# BandpassedGainAmpSMTMounthole.net
KiCad netlist of a schematic drawn in EAGLE
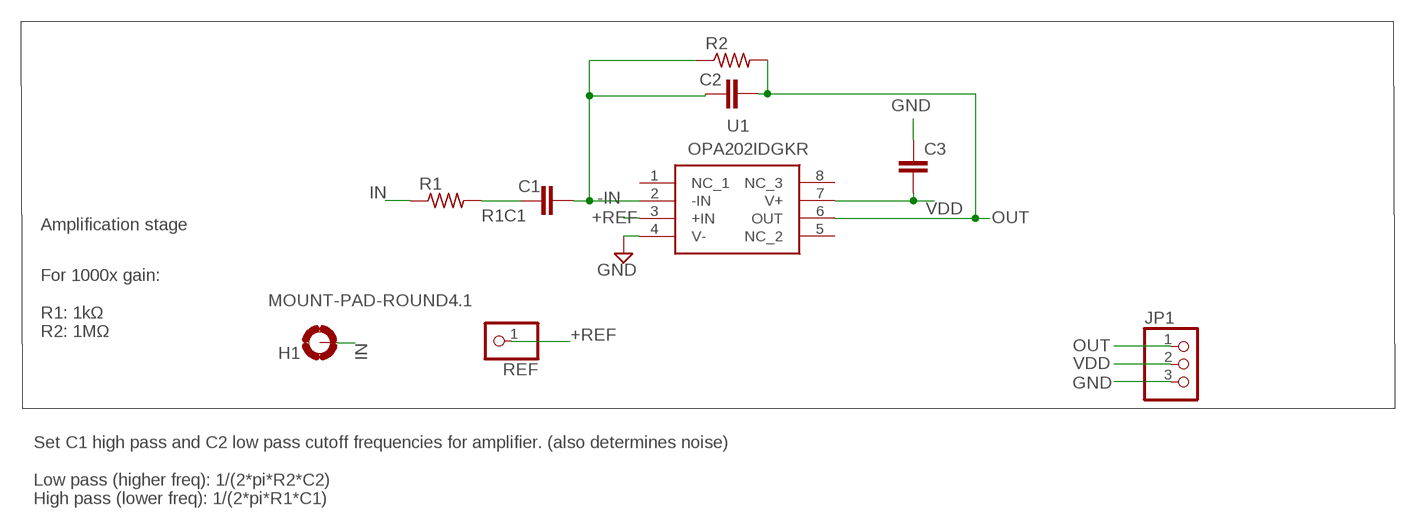
[diagram p0: schematic, sheet 1]

(export (version "E")
  (design (tool "Eeschema 10.0.6"))
  (components
    (comp (ref "C1")
      (value "C-EUC0402")
      (footprint "eagle-import:C0402")
      (libsource (lib "eagle-import") (part "C-EUC0402"))
    )
    (comp (ref "C2")
      (value "C-EUC0402")
      (footprint "eagle-import:C0402")
      (libsource (lib "eagle-import") (part "C-EUC0402"))
    )
    (comp (ref "C3")
      (value "C-EUC0402")
      (footprint "eagle-import:C0402")
      (libsource (lib "eagle-import") (part "C-EUC0402"))
    )
    (comp (ref "H1")
      (value "MOUNT-PAD-ROUND4.1")
      (footprint "eagle-import:4,1-PAD")
      (libsource (lib "eagle-import") (part "MOUNT-PAD-ROUND4.1"))
    )
    (comp (ref "JP1")
      (value "PINHD-1X3")
      (footprint "eagle-import:1X03")
      (libsource (lib "eagle-import") (part "PINHD-1X3"))
    )
    (comp (ref "R1")
      (value "R-US_R0402")
      (footprint "eagle-import:R0402")
      (libsource (lib "eagle-import") (part "R-US_R0402"))
    )
    (comp (ref "R2")
      (value "R-US_R0402")
      (footprint "eagle-import:R0402")
      (libsource (lib "eagle-import") (part "R-US_R0402"))
    )
    (comp (ref "REF")
      (value "PINHD-1X1")
      (footprint "eagle-import:1X01")
      (libsource (lib "eagle-import") (part "PINHD-1X1"))
    )
    (comp (ref "U1")
      (value "OPA202IDGKR")
      (footprint "eagle-import:SOP65P490X110-8N")
      (fields (field (name "MOUSER_PART_NUMBER") "595-OPA202IDGKR"))
      (libsource (lib "eagle-import") (part "OPA202IDGKR"))
    )
  )
  (nets
    (net (code "1") (name "/+REF") (class "Default")
      (node (ref "REF") (pin "1") (pinfunction "1_1") (pintype "passive"))
      (node (ref "U1") (pin "3") (pinfunction "+IN_3") (pintype "bidirectional"))
    )
    (net (code "2") (name "/-IN") (class "Default")
      (node (ref "C1") (pin "2") (pinfunction "2_2") (pintype "passive"))
      (node (ref "C2") (pin "1") (pinfunction "1_1") (pintype "passive"))
      (node (ref "R2") (pin "1") (pinfunction "1_1") (pintype "passive"))
      (node (ref "U1") (pin "2") (pinfunction "-IN_2") (pintype "bidirectional"))
    )
    (net (code "3") (name "/IN") (class "Default")
      (node (ref "H1") (pin "B4,1") (pinfunction "MOUNT_B4,1") (pintype "passive"))
      (node (ref "R1") (pin "1") (pinfunction "1_1") (pintype "passive"))
    )
    (net (code "4") (name "/OUT") (class "Default")
      (node (ref "C2") (pin "2") (pinfunction "2_2") (pintype "passive"))
      (node (ref "JP1") (pin "1") (pinfunction "1_1") (pintype "passive"))
      (node (ref "R2") (pin "2") (pinfunction "2_2") (pintype "passive"))
      (node (ref "U1") (pin "6") (pinfunction "OUT_6") (pintype "bidirectional"))
    )
    (net (code "5") (name "/R1C1") (class "Default")
      (node (ref "C1") (pin "1") (pinfunction "1_1") (pintype "passive"))
      (node (ref "R1") (pin "2") (pinfunction "2_2") (pintype "passive"))
    )
    (net (code "6") (name "/VDD") (class "Default")
      (node (ref "C3") (pin "2") (pinfunction "2_2") (pintype "passive"))
      (node (ref "JP1") (pin "2") (pinfunction "2_2") (pintype "passive"))
      (node (ref "U1") (pin "7") (pinfunction "V+_7") (pintype "bidirectional"))
    )
    (net (code "7") (name "GND") (class "Default")
      (node (ref "C3") (pin "1") (pinfunction "1_1") (pintype "passive"))
      (node (ref "JP1") (pin "3") (pinfunction "3_3") (pintype "passive"))
      (node (ref "U1") (pin "4") (pinfunction "V-_4") (pintype "bidirectional"))
    )
    (net (code "8") (name "unconnected-(U1-NC_1-Pad1)") (class "Default")
      (node (ref "U1") (pin "1") (pinfunction "NC_1_1") (pintype "bidirectional"))
    )
    (net (code "9") (name "unconnected-(U1-NC_2-Pad5)") (class "Default")
      (node (ref "U1") (pin "5") (pinfunction "NC_2_5") (pintype "bidirectional"))
    )
    (net (code "10") (name "unconnected-(U1-NC_3-Pad8)") (class "Default")
      (node (ref "U1") (pin "8") (pinfunction "NC_3_8") (pintype "bidirectional"))
    )
  )
)
